# RF_Nano_Controller_Update_Schematic.net
KiCad netlist of a schematic drawn in EasyEDA
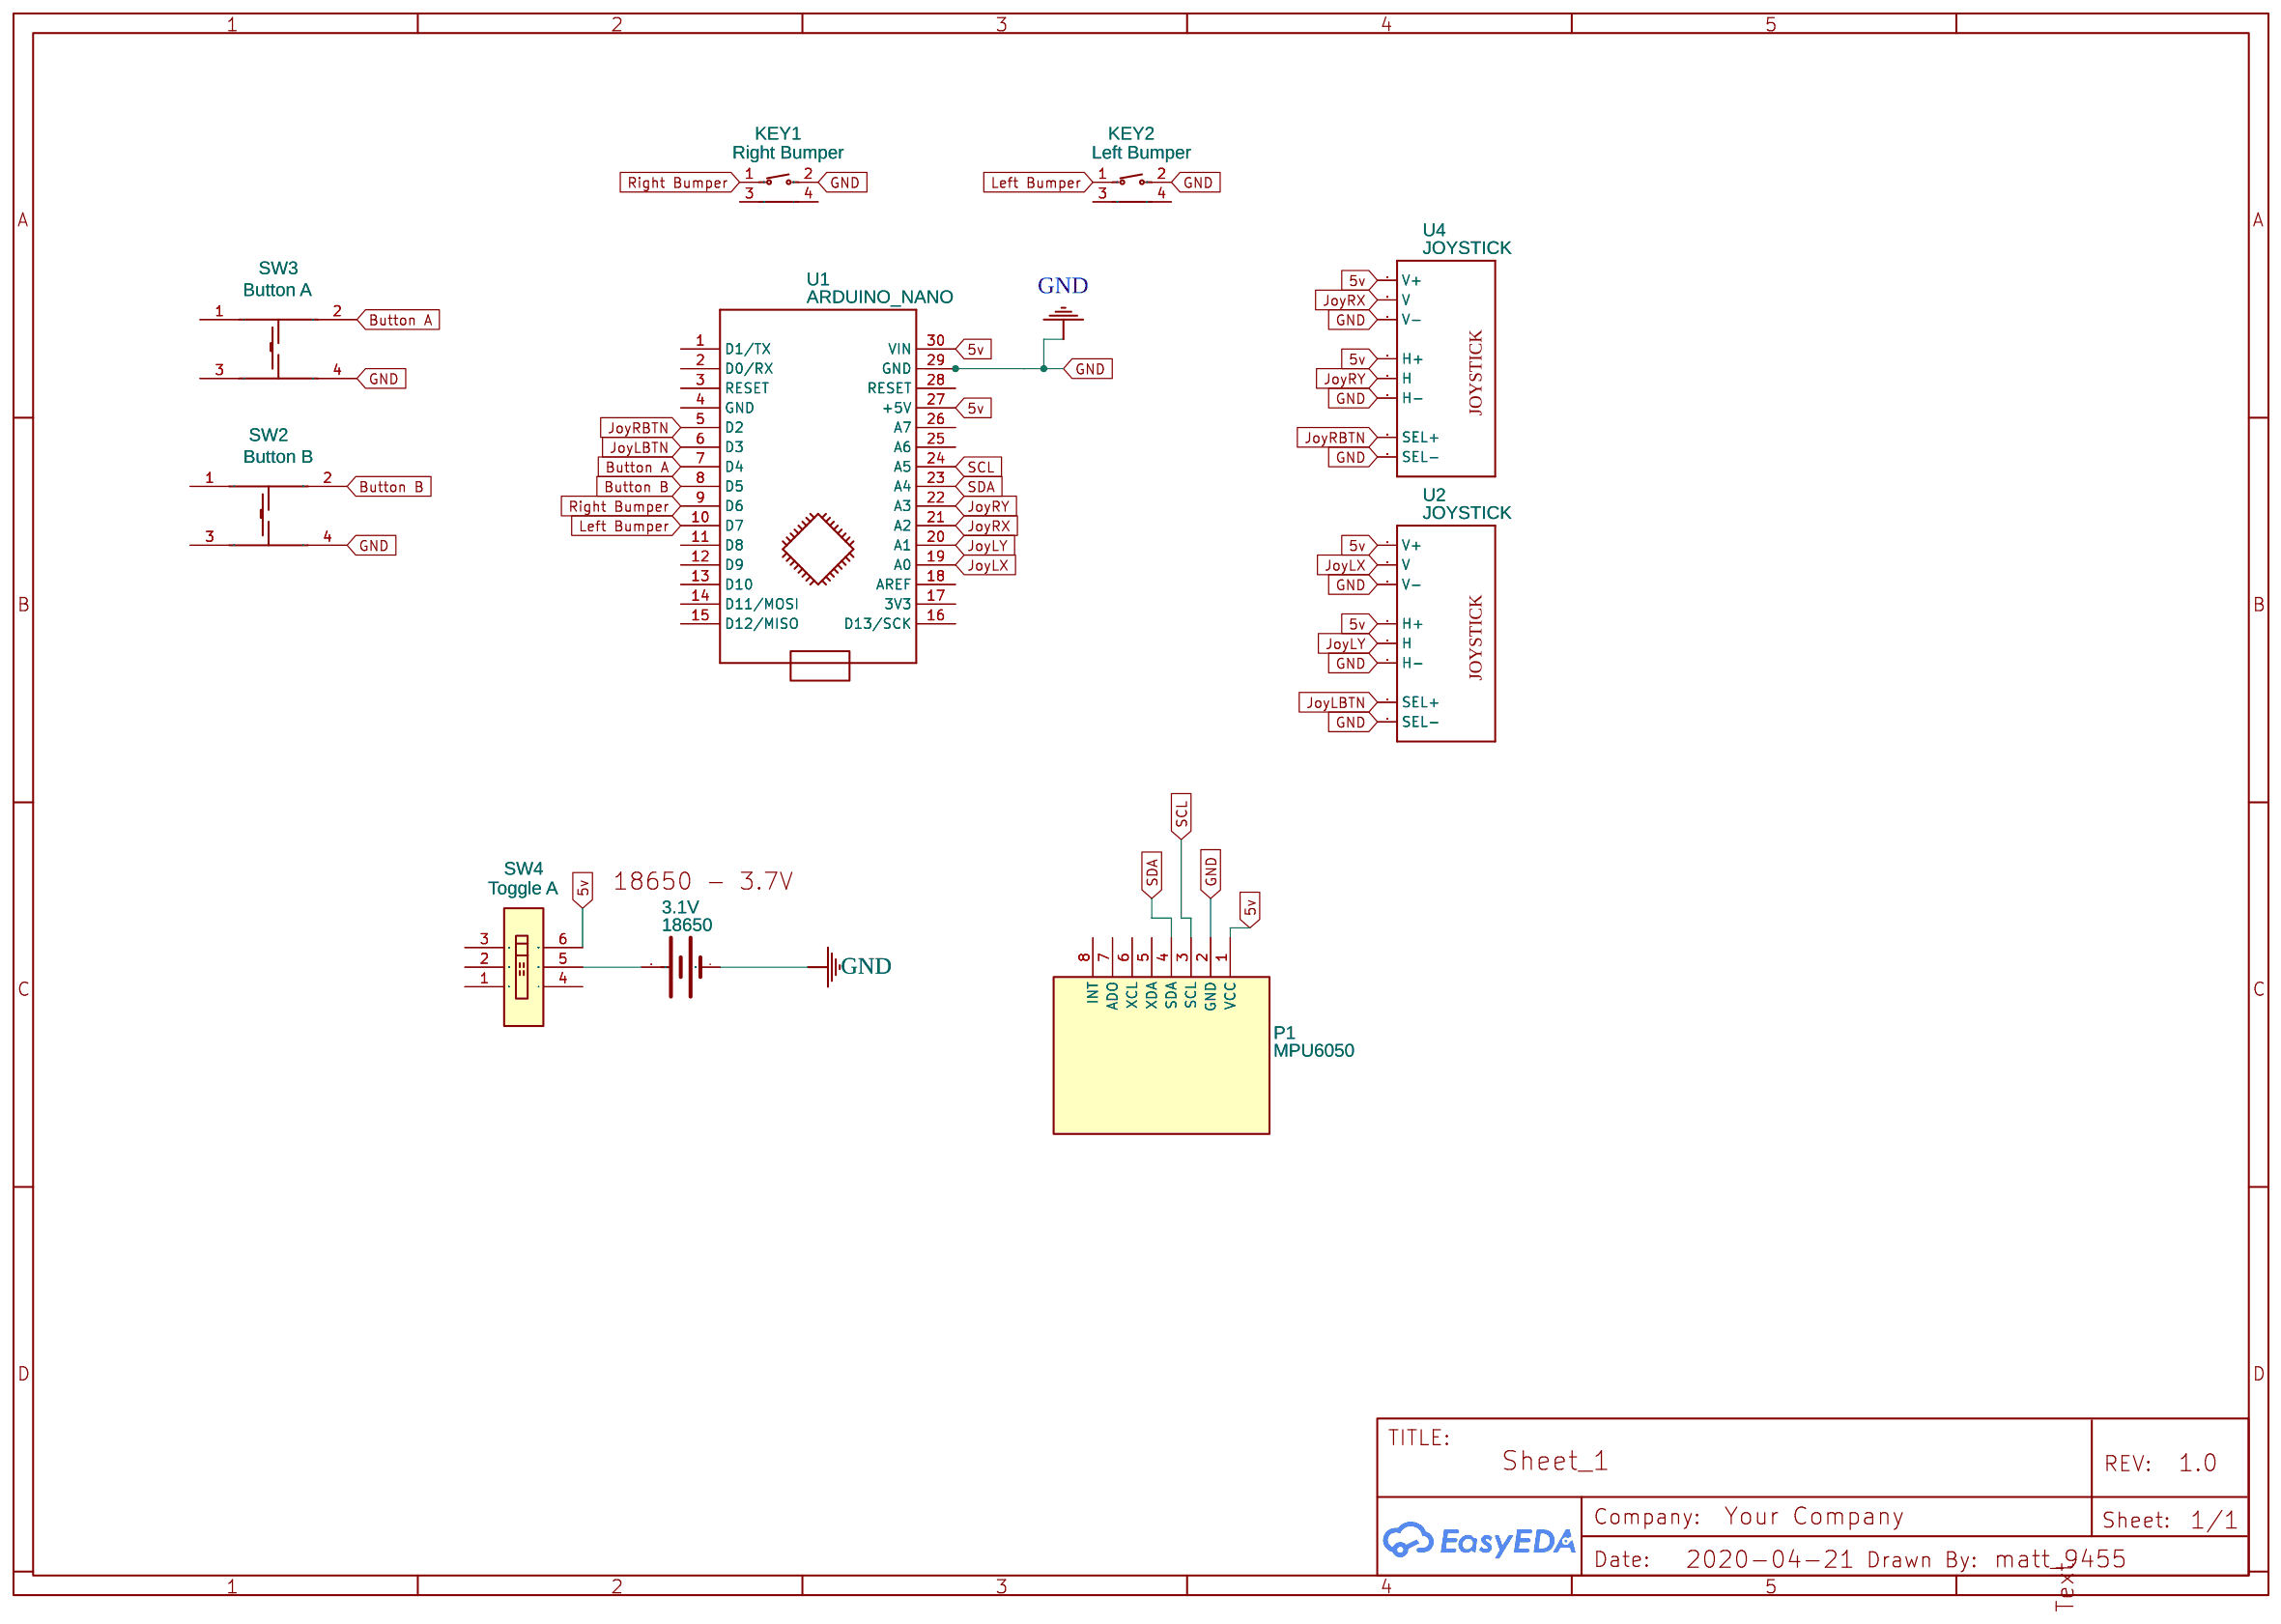
[diagram p0: schematic sheet]

(export (version "E")
  (design (tool "Eeschema 10.0.6"))
  (components
    (comp (ref "3.1V") (value "18650") (libsource (lib "") (part "18650")))
    (comp (ref "KEY1")
      (value "Right Bumper")
      (fields
        (field (name "BOM_Manufacturer Part") "Switch,6*6*5Plastic head,260G, 0.25mm,Side foot")
        (field (name "BOM_Supplier Part") "C71832")
      )
      (libsource (lib "") (part "Switch,6*6*5Plastic head,260G, 0.25mm,Side foot"))
    )
    (comp (ref "KEY2")
      (value "Left Bumper")
      (fields
        (field (name "BOM_Manufacturer Part") "Switch,6*6*5Plastic head,260G, 0.25mm,Side foot")
        (field (name "BOM_Supplier Part") "C71832")
      )
      (libsource (lib "") (part "Switch,6*6*5Plastic head,260G, 0.25mm,Side foot"))
    )
    (comp (ref "P1") (value "MPU6050") (libsource (lib "") (part "MPU6050")))
    (comp (ref "SW2")
      (value "Button B")
      (fields
        (field (name "BOM_Manufacturer Part") "K2-1841DP-H4SW-02")
        (field (name "BOM_Supplier Part") "C145864")
      )
      (libsource (lib "") (part "K2-1841DP-H4SW-02"))
    )
    (comp (ref "SW3")
      (value "Button A")
      (fields
        (field (name "BOM_Manufacturer Part") "K2-1841DP-H4SW-02")
        (field (name "BOM_Supplier Part") "C145864")
      )
      (libsource (lib "") (part "K2-1841DP-H4SW-02"))
    )
    (comp (ref "SW4")
      (value "Toggle A")
      (fields
        (field (name "BOM_Manufacturer Part") "SSSS213202")
        (field (name "BOM_Supplier Part") "C115375")
      )
      (libsource (lib "") (part "SSSS213202"))
    )
    (comp (ref "U1") (value "ARDUINO_NANO") (libsource (lib "") (part "ARDUINO_NANO")))
    (comp (ref "U2") (value "JOYSTICK") (libsource (lib "") (part "JOYSTICK")))
    (comp (ref "U4") (value "JOYSTICK") (libsource (lib "") (part "JOYSTICK")))
  )
  (nets
    (net (code "1") (name "5v") (class "Default")
      (node (ref "P1") (pin "1") (pinfunction "VCC_1") (pintype "unspecified"))
      (node (ref "SW4") (pin "6") (pinfunction "6_6") (pintype "input"))
      (node (ref "U1") (pin "27") (pinfunction "+5V_27") (pintype "unspecified"))
      (node (ref "U1") (pin "30") (pinfunction "VIN_30") (pintype "unspecified"))
      (node (ref "U2") (pin "H1") (pinfunction "H+_H1") (pintype "unspecified"))
      (node (ref "U2") (pin "V1") (pinfunction "V+_V1") (pintype "unspecified"))
      (node (ref "U4") (pin "H1") (pinfunction "H+_H1") (pintype "unspecified"))
      (node (ref "U4") (pin "V1") (pinfunction "V+_V1") (pintype "unspecified"))
    )
    (net (code "2") (name "Button A") (class "Default")
      (node (ref "SW3") (pin "2") (pinfunction "2_2") (pintype "unspecified"))
      (node (ref "U1") (pin "7") (pinfunction "D4_7") (pintype "unspecified"))
    )
    (net (code "3") (name "Button B") (class "Default")
      (node (ref "SW2") (pin "2") (pinfunction "2_2") (pintype "unspecified"))
      (node (ref "U1") (pin "8") (pinfunction "D5_8") (pintype "unspecified"))
    )
    (net (code "4") (name "GND") (class "Default")
      (node (ref "3.1V") (pin "-") (pinfunction "1_-") (pintype "passive"))
      (node (ref "KEY1") (pin "2") (pinfunction "2_2") (pintype "unspecified"))
      (node (ref "KEY2") (pin "2") (pinfunction "2_2") (pintype "unspecified"))
      (node (ref "P1") (pin "2") (pinfunction "GND_2") (pintype "unspecified"))
      (node (ref "SW2") (pin "4") (pinfunction "4_4") (pintype "unspecified"))
      (node (ref "SW3") (pin "4") (pinfunction "4_4") (pintype "unspecified"))
      (node (ref "U1") (pin "29") (pinfunction "GND_29") (pintype "unspecified"))
      (node (ref "U2") (pin "B2A") (pinfunction "SEL-_B2A") (pintype "unspecified"))
      (node (ref "U2") (pin "H3") (pinfunction "H-_H3") (pintype "unspecified"))
      (node (ref "U2") (pin "V3") (pinfunction "V-_V3") (pintype "unspecified"))
      (node (ref "U4") (pin "B2A") (pinfunction "SEL-_B2A") (pintype "unspecified"))
      (node (ref "U4") (pin "H3") (pinfunction "H-_H3") (pintype "unspecified"))
      (node (ref "U4") (pin "V3") (pinfunction "V-_V3") (pintype "unspecified"))
    )
    (net (code "5") (name "JoyLBTN") (class "Default")
      (node (ref "U1") (pin "6") (pinfunction "D3_6") (pintype "unspecified"))
      (node (ref "U2") (pin "B1A") (pinfunction "SEL+_B1A") (pintype "unspecified"))
    )
    (net (code "6") (name "JoyLX") (class "Default")
      (node (ref "U1") (pin "19") (pinfunction "A0_19") (pintype "unspecified"))
      (node (ref "U2") (pin "V2") (pinfunction "V_V2") (pintype "unspecified"))
    )
    (net (code "7") (name "JoyLY") (class "Default")
      (node (ref "U1") (pin "20") (pinfunction "A1_20") (pintype "unspecified"))
      (node (ref "U2") (pin "H2") (pinfunction "H_H2") (pintype "unspecified"))
    )
    (net (code "8") (name "JoyRBTN") (class "Default")
      (node (ref "U1") (pin "5") (pinfunction "D2_5") (pintype "unspecified"))
      (node (ref "U4") (pin "B1A") (pinfunction "SEL+_B1A") (pintype "unspecified"))
    )
    (net (code "9") (name "JoyRX") (class "Default")
      (node (ref "U1") (pin "21") (pinfunction "A2_21") (pintype "unspecified"))
      (node (ref "U4") (pin "V2") (pinfunction "V_V2") (pintype "unspecified"))
    )
    (net (code "10") (name "JoyRY") (class "Default")
      (node (ref "U1") (pin "22") (pinfunction "A3_22") (pintype "unspecified"))
      (node (ref "U4") (pin "H2") (pinfunction "H_H2") (pintype "unspecified"))
    )
    (net (code "11") (name "Left Bumper") (class "Default")
      (node (ref "KEY2") (pin "1") (pinfunction "1_1") (pintype "unspecified"))
      (node (ref "U1") (pin "10") (pinfunction "D7_10") (pintype "unspecified"))
    )
    (net (code "12") (name "Net-(3.1V-2)") (class "Default")
      (node (ref "3.1V") (pin "+") (pinfunction "2_+") (pintype "passive"))
      (node (ref "SW4") (pin "5") (pinfunction "5_5") (pintype "input"))
    )
    (net (code "13") (name "Right Bumper") (class "Default")
      (node (ref "KEY1") (pin "1") (pinfunction "1_1") (pintype "unspecified"))
      (node (ref "U1") (pin "9") (pinfunction "D6_9") (pintype "unspecified"))
    )
    (net (code "14") (name "SCL") (class "Default")
      (node (ref "P1") (pin "3") (pinfunction "SCL_3") (pintype "unspecified"))
      (node (ref "U1") (pin "24") (pinfunction "A5_24") (pintype "unspecified"))
    )
    (net (code "15") (name "SDA") (class "Default")
      (node (ref "P1") (pin "4") (pinfunction "SDA_4") (pintype "unspecified"))
      (node (ref "U1") (pin "23") (pinfunction "A4_23") (pintype "unspecified"))
    )
    (net (code "16") (name "unconnected-(KEY1-Pad3)") (class "Default")
      (node (ref "KEY1") (pin "3") (pinfunction "3_3") (pintype "unspecified"))
    )
    (net (code "17") (name "unconnected-(KEY1-Pad4)") (class "Default")
      (node (ref "KEY1") (pin "4") (pinfunction "4_4") (pintype "unspecified"))
    )
    (net (code "18") (name "unconnected-(KEY2-Pad3)") (class "Default")
      (node (ref "KEY2") (pin "3") (pinfunction "3_3") (pintype "unspecified"))
    )
    (net (code "19") (name "unconnected-(KEY2-Pad4)") (class "Default")
      (node (ref "KEY2") (pin "4") (pinfunction "4_4") (pintype "unspecified"))
    )
    (net (code "20") (name "unconnected-(P1-ADO-Pad7)") (class "Default")
      (node (ref "P1") (pin "7") (pinfunction "ADO_7") (pintype "unspecified"))
    )
    (net (code "21") (name "unconnected-(P1-INT-Pad8)") (class "Default")
      (node (ref "P1") (pin "8") (pinfunction "INT_8") (pintype "unspecified"))
    )
    (net (code "22") (name "unconnected-(P1-XCL-Pad6)") (class "Default")
      (node (ref "P1") (pin "6") (pinfunction "XCL_6") (pintype "unspecified"))
    )
    (net (code "23") (name "unconnected-(P1-XDA-Pad5)") (class "Default")
      (node (ref "P1") (pin "5") (pinfunction "XDA_5") (pintype "unspecified"))
    )
    (net (code "24") (name "unconnected-(SW2-Pad1)") (class "Default")
      (node (ref "SW2") (pin "1") (pinfunction "1_1") (pintype "unspecified"))
    )
    (net (code "25") (name "unconnected-(SW2-Pad3)") (class "Default")
      (node (ref "SW2") (pin "3") (pinfunction "3_3") (pintype "unspecified"))
    )
    (net (code "26") (name "unconnected-(SW3-Pad1)") (class "Default")
      (node (ref "SW3") (pin "1") (pinfunction "1_1") (pintype "unspecified"))
    )
    (net (code "27") (name "unconnected-(SW3-Pad3)") (class "Default")
      (node (ref "SW3") (pin "3") (pinfunction "3_3") (pintype "unspecified"))
    )
    (net (code "28") (name "unconnected-(SW4-Pad1)") (class "Default")
      (node (ref "SW4") (pin "1") (pinfunction "1_1") (pintype "input"))
    )
    (net (code "29") (name "unconnected-(SW4-Pad2)") (class "Default")
      (node (ref "SW4") (pin "2") (pinfunction "2_2") (pintype "input"))
    )
    (net (code "30") (name "unconnected-(SW4-Pad3)") (class "Default")
      (node (ref "SW4") (pin "3") (pinfunction "3_3") (pintype "input"))
    )
    (net (code "31") (name "unconnected-(SW4-Pad4)") (class "Default")
      (node (ref "SW4") (pin "4") (pinfunction "4_4") (pintype "input"))
    )
    (net (code "32") (name "unconnected-(U1-3V3-Pad17)") (class "Default")
      (node (ref "U1") (pin "17") (pinfunction "3V3_17") (pintype "unspecified"))
    )
    (net (code "33") (name "unconnected-(U1-A6-Pad25)") (class "Default")
      (node (ref "U1") (pin "25") (pinfunction "A6_25") (pintype "unspecified"))
    )
    (net (code "34") (name "unconnected-(U1-A7-Pad26)") (class "Default")
      (node (ref "U1") (pin "26") (pinfunction "A7_26") (pintype "unspecified"))
    )
    (net (code "35") (name "unconnected-(U1-AREF-Pad18)") (class "Default")
      (node (ref "U1") (pin "18") (pinfunction "AREF_18") (pintype "unspecified"))
    )
    (net (code "36") (name "unconnected-(U1-D0{slash}RX-Pad2)") (class "Default")
      (node (ref "U1") (pin "2") (pinfunction "D0/RX_2") (pintype "unspecified"))
    )
    (net (code "37") (name "unconnected-(U1-D1{slash}TX-Pad1)") (class "Default")
      (node (ref "U1") (pin "1") (pinfunction "D1/TX_1") (pintype "unspecified"))
    )
    (net (code "38") (name "unconnected-(U1-D8-Pad11)") (class "Default")
      (node (ref "U1") (pin "11") (pinfunction "D8_11") (pintype "unspecified"))
    )
    (net (code "39") (name "unconnected-(U1-D9-Pad12)") (class "Default")
      (node (ref "U1") (pin "12") (pinfunction "D9_12") (pintype "unspecified"))
    )
    (net (code "40") (name "unconnected-(U1-D10-Pad13)") (class "Default")
      (node (ref "U1") (pin "13") (pinfunction "D10_13") (pintype "unspecified"))
    )
    (net (code "41") (name "unconnected-(U1-D11{slash}MOSI-Pad14)") (class "Default")
      (node (ref "U1") (pin "14") (pinfunction "D11/MOSI_14") (pintype "unspecified"))
    )
    (net (code "42") (name "unconnected-(U1-D12{slash}MISO-Pad15)") (class "Default")
      (node (ref "U1") (pin "15") (pinfunction "D12/MISO_15") (pintype "unspecified"))
    )
    (net (code "43") (name "unconnected-(U1-D13{slash}SCK-Pad16)") (class "Default")
      (node (ref "U1") (pin "16") (pinfunction "D13/SCK_16") (pintype "unspecified"))
    )
    (net (code "44") (name "unconnected-(U1-GND-Pad4)") (class "Default")
      (node (ref "U1") (pin "4") (pinfunction "GND_4") (pintype "unspecified"))
    )
    (net (code "45") (name "unconnected-(U1-RESET-Pad3)") (class "Default")
      (node (ref "U1") (pin "3") (pinfunction "RESET_3") (pintype "unspecified"))
    )
    (net (code "46") (name "unconnected-(U1-RESET-Pad28)") (class "Default")
      (node (ref "U1") (pin "28") (pinfunction "RESET_28") (pintype "unspecified"))
    )
  )
)
